# Carte_USB.net
KiCad netlist of a schematic drawn in EAGLE
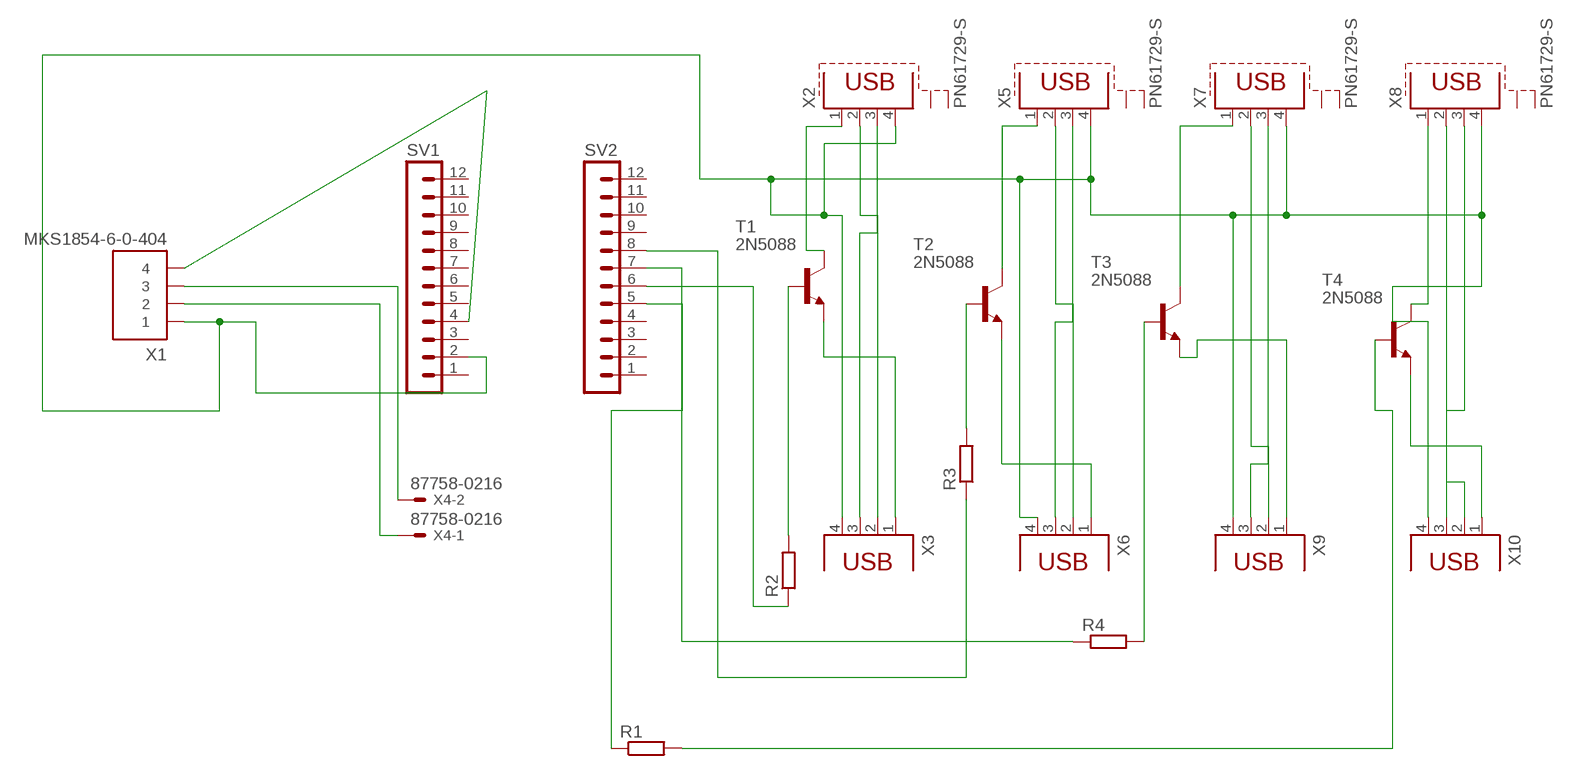
[diagram p0: schematic, sheet 1]

(export (version "E")
  (design (tool "Eeschema 10.0.6"))
  (components
    (comp (ref "R1")
      (value "R-EU_0207/10")
      (footprint "eagle-import:0207_10")
      (libsource (lib "eagle-import") (part "R-EU_0207/10"))
    )
    (comp (ref "R2")
      (value "R-EU_0207/10")
      (footprint "eagle-import:0207_10")
      (libsource (lib "eagle-import") (part "R-EU_0207/10"))
    )
    (comp (ref "R3")
      (value "R-EU_0207/10")
      (footprint "eagle-import:0207_10")
      (libsource (lib "eagle-import") (part "R-EU_0207/10"))
    )
    (comp (ref "R4")
      (value "R-EU_0207/10")
      (footprint "eagle-import:0207_10")
      (libsource (lib "eagle-import") (part "R-EU_0207/10"))
    )
    (comp (ref "SV1")
      (value "MA12-1")
      (footprint "eagle-import:MA12-1")
      (libsource (lib "eagle-import") (part "MA12-1"))
    )
    (comp (ref "SV2")
      (value "MA12-1")
      (footprint "eagle-import:MA12-1")
      (libsource (lib "eagle-import") (part "MA12-1"))
    )
    (comp (ref "T1")
      (value "2N5088")
      (footprint "eagle-import:TO92")
      (libsource (lib "eagle-import") (part "2N5088"))
    )
    (comp (ref "T2")
      (value "2N5088")
      (footprint "eagle-import:TO92")
      (libsource (lib "eagle-import") (part "2N5088"))
    )
    (comp (ref "T3")
      (value "2N5088")
      (footprint "eagle-import:TO92")
      (libsource (lib "eagle-import") (part "2N5088"))
    )
    (comp (ref "T4")
      (value "2N5088")
      (footprint "eagle-import:TO92")
      (libsource (lib "eagle-import") (part "2N5088"))
    )
    (comp (ref "X1")
      (value "MKS1854-6-0-404")
      (footprint "eagle-import:MKS1854-6-0-404")
      (libsource (lib "eagle-import") (part "MKS1854-6-0-404"))
    )
    (comp (ref "X2")
      (value "PN61729-S")
      (footprint "eagle-import:PN61729-S")
      (libsource (lib "eagle-import") (part "PN61729-S"))
    )
    (comp (ref "X3")
      (value "PN87520")
      (footprint "eagle-import:PN87520")
      (libsource (lib "eagle-import") (part "PN87520"))
    )
    (comp (ref "X4")
      (value "87758-0216")
      (footprint "eagle-import:87758-0216")
      (libsource (lib "eagle-import") (part "87758-0216"))
    )
    (comp (ref "X5")
      (value "PN61729-S")
      (footprint "eagle-import:PN61729-S")
      (libsource (lib "eagle-import") (part "PN61729-S"))
    )
    (comp (ref "X6")
      (value "PN87520")
      (footprint "eagle-import:PN87520")
      (libsource (lib "eagle-import") (part "PN87520"))
    )
    (comp (ref "X7")
      (value "PN61729-S")
      (footprint "eagle-import:PN61729-S")
      (libsource (lib "eagle-import") (part "PN61729-S"))
    )
    (comp (ref "X8")
      (value "PN61729-S")
      (footprint "eagle-import:PN61729-S")
      (libsource (lib "eagle-import") (part "PN61729-S"))
    )
    (comp (ref "X9")
      (value "PN87520")
      (footprint "eagle-import:PN87520")
      (libsource (lib "eagle-import") (part "PN87520"))
    )
    (comp (ref "X10")
      (value "PN87520")
      (footprint "eagle-import:PN87520")
      (libsource (lib "eagle-import") (part "PN87520"))
    )
  )
  (nets
    (net (code "1") (name "Net-(R1-Pad1)") (class "Default")
      (node (ref "R1") (pin "1") (pinfunction "1_1") (pintype "passive"))
      (node (ref "SV2") (pin "5") (pinfunction "5_5") (pintype "passive"))
    )
    (net (code "2") (name "Net-(R2-Pad1)") (class "Default")
      (node (ref "R2") (pin "1") (pinfunction "1_1") (pintype "passive"))
      (node (ref "SV2") (pin "6") (pinfunction "6_6") (pintype "passive"))
    )
    (net (code "3") (name "Net-(R3-Pad1)") (class "Default")
      (node (ref "R3") (pin "1") (pinfunction "1_1") (pintype "passive"))
      (node (ref "SV2") (pin "8") (pinfunction "8_8") (pintype "passive"))
    )
    (net (code "4") (name "Net-(R4-Pad1)") (class "Default")
      (node (ref "R4") (pin "1") (pinfunction "1_1") (pintype "passive"))
      (node (ref "SV2") (pin "7") (pinfunction "7_7") (pintype "passive"))
    )
    (net (code "5") (name "Net-(SV1-Pad2)") (class "Default")
      (node (ref "SV1") (pin "2") (pinfunction "2_2") (pintype "passive"))
      (node (ref "X1") (pin "1") (pinfunction "1_1") (pintype "input"))
      (node (ref "X10") (pin "4") (pinfunction "4_4") (pintype "passive"))
      (node (ref "X2") (pin "4") (pinfunction "4_4") (pintype "passive"))
      (node (ref "X3") (pin "4") (pinfunction "4_4") (pintype "passive"))
      (node (ref "X5") (pin "4") (pinfunction "4_4") (pintype "passive"))
      (node (ref "X6") (pin "4") (pinfunction "4_4") (pintype "passive"))
      (node (ref "X7") (pin "4") (pinfunction "4_4") (pintype "passive"))
      (node (ref "X8") (pin "4") (pinfunction "4_4") (pintype "passive"))
      (node (ref "X9") (pin "4") (pinfunction "4_4") (pintype "passive"))
    )
    (net (code "6") (name "Net-(SV1-Pad4)") (class "Default")
      (node (ref "SV1") (pin "4") (pinfunction "4_4") (pintype "passive"))
      (node (ref "X1") (pin "4") (pinfunction "4_4") (pintype "input"))
    )
    (net (code "7") (name "Net-(T1-B)") (class "Default")
      (node (ref "R2") (pin "2") (pinfunction "2_2") (pintype "passive"))
      (node (ref "T1") (pin "2") (pinfunction "B_2") (pintype "passive"))
    )
    (net (code "8") (name "Net-(T1-C)") (class "Default")
      (node (ref "T1") (pin "1") (pinfunction "C_1") (pintype "passive"))
      (node (ref "X2") (pin "1") (pinfunction "1_1") (pintype "passive"))
    )
    (net (code "9") (name "Net-(T1-E)") (class "Default")
      (node (ref "T1") (pin "3") (pinfunction "E_3") (pintype "passive"))
      (node (ref "X3") (pin "1") (pinfunction "1_1") (pintype "passive"))
    )
    (net (code "10") (name "Net-(T2-B)") (class "Default")
      (node (ref "R3") (pin "2") (pinfunction "2_2") (pintype "passive"))
      (node (ref "T2") (pin "2") (pinfunction "B_2") (pintype "passive"))
    )
    (net (code "11") (name "Net-(T2-C)") (class "Default")
      (node (ref "T2") (pin "1") (pinfunction "C_1") (pintype "passive"))
      (node (ref "X5") (pin "1") (pinfunction "1_1") (pintype "passive"))
    )
    (net (code "12") (name "Net-(T2-E)") (class "Default")
      (node (ref "T2") (pin "3") (pinfunction "E_3") (pintype "passive"))
      (node (ref "X6") (pin "1") (pinfunction "1_1") (pintype "passive"))
    )
    (net (code "13") (name "Net-(T3-B)") (class "Default")
      (node (ref "R4") (pin "2") (pinfunction "2_2") (pintype "passive"))
      (node (ref "T3") (pin "2") (pinfunction "B_2") (pintype "passive"))
    )
    (net (code "14") (name "Net-(T3-C)") (class "Default")
      (node (ref "T3") (pin "1") (pinfunction "C_1") (pintype "passive"))
      (node (ref "X7") (pin "1") (pinfunction "1_1") (pintype "passive"))
    )
    (net (code "15") (name "Net-(T3-E)") (class "Default")
      (node (ref "T3") (pin "3") (pinfunction "E_3") (pintype "passive"))
      (node (ref "X9") (pin "1") (pinfunction "1_1") (pintype "passive"))
    )
    (net (code "16") (name "Net-(T4-B)") (class "Default")
      (node (ref "R1") (pin "2") (pinfunction "2_2") (pintype "passive"))
      (node (ref "T4") (pin "2") (pinfunction "B_2") (pintype "passive"))
    )
    (net (code "17") (name "Net-(T4-C)") (class "Default")
      (node (ref "T4") (pin "1") (pinfunction "C_1") (pintype "passive"))
      (node (ref "X8") (pin "1") (pinfunction "1_1") (pintype "passive"))
    )
    (net (code "18") (name "Net-(T4-E)") (class "Default")
      (node (ref "T4") (pin "3") (pinfunction "E_3") (pintype "passive"))
      (node (ref "X10") (pin "1") (pinfunction "1_1") (pintype "passive"))
    )
    (net (code "19") (name "Net-(X2-Pad2)") (class "Default")
      (node (ref "X2") (pin "2") (pinfunction "2_2") (pintype "passive"))
      (node (ref "X3") (pin "2") (pinfunction "2_2") (pintype "passive"))
    )
    (net (code "20") (name "Net-(X2-Pad3)") (class "Default")
      (node (ref "X2") (pin "3") (pinfunction "3_3") (pintype "passive"))
      (node (ref "X3") (pin "3") (pinfunction "3_3") (pintype "passive"))
    )
    (net (code "21") (name "Net-(X4A-S)") (class "Default")
      (node (ref "X1") (pin "2") (pinfunction "2_2") (pintype "input"))
      (node (ref "X4") (pin "1") (pinfunction "S_1") (pintype "passive"))
    )
    (net (code "22") (name "Net-(X4B-S)") (class "Default")
      (node (ref "X1") (pin "3") (pinfunction "3_3") (pintype "input"))
      (node (ref "X4") (pin "2") (pinfunction "S_2") (pintype "passive"))
    )
    (net (code "23") (name "Net-(X5-Pad2)") (class "Default")
      (node (ref "X5") (pin "2") (pinfunction "2_2") (pintype "passive"))
      (node (ref "X6") (pin "2") (pinfunction "2_2") (pintype "passive"))
    )
    (net (code "24") (name "Net-(X5-Pad3)") (class "Default")
      (node (ref "X5") (pin "3") (pinfunction "3_3") (pintype "passive"))
      (node (ref "X6") (pin "3") (pinfunction "3_3") (pintype "passive"))
    )
    (net (code "25") (name "Net-(X7-Pad2)") (class "Default")
      (node (ref "X7") (pin "2") (pinfunction "2_2") (pintype "passive"))
      (node (ref "X9") (pin "2") (pinfunction "2_2") (pintype "passive"))
    )
    (net (code "26") (name "Net-(X7-Pad3)") (class "Default")
      (node (ref "X7") (pin "3") (pinfunction "3_3") (pintype "passive"))
      (node (ref "X9") (pin "3") (pinfunction "3_3") (pintype "passive"))
    )
    (net (code "27") (name "Net-(X10-Pad2)") (class "Default")
      (node (ref "X10") (pin "2") (pinfunction "2_2") (pintype "passive"))
      (node (ref "X8") (pin "2") (pinfunction "2_2") (pintype "passive"))
    )
    (net (code "28") (name "Net-(X10-Pad3)") (class "Default")
      (node (ref "X10") (pin "3") (pinfunction "3_3") (pintype "passive"))
      (node (ref "X8") (pin "3") (pinfunction "3_3") (pintype "passive"))
    )
    (net (code "29") (name "unconnected-(SV1-Pad1)") (class "Default")
      (node (ref "SV1") (pin "1") (pinfunction "1_1") (pintype "passive"))
    )
    (net (code "30") (name "unconnected-(SV1-Pad3)") (class "Default")
      (node (ref "SV1") (pin "3") (pinfunction "3_3") (pintype "passive"))
    )
    (net (code "31") (name "unconnected-(SV1-Pad5)") (class "Default")
      (node (ref "SV1") (pin "5") (pinfunction "5_5") (pintype "passive"))
    )
    (net (code "32") (name "unconnected-(SV1-Pad6)") (class "Default")
      (node (ref "SV1") (pin "6") (pinfunction "6_6") (pintype "passive"))
    )
    (net (code "33") (name "unconnected-(SV1-Pad7)") (class "Default")
      (node (ref "SV1") (pin "7") (pinfunction "7_7") (pintype "passive"))
    )
    (net (code "34") (name "unconnected-(SV1-Pad8)") (class "Default")
      (node (ref "SV1") (pin "8") (pinfunction "8_8") (pintype "passive"))
    )
    (net (code "35") (name "unconnected-(SV1-Pad9)") (class "Default")
      (node (ref "SV1") (pin "9") (pinfunction "9_9") (pintype "passive"))
    )
    (net (code "36") (name "unconnected-(SV1-Pad10)") (class "Default")
      (node (ref "SV1") (pin "10") (pinfunction "10_10") (pintype "passive"))
    )
    (net (code "37") (name "unconnected-(SV1-Pad11)") (class "Default")
      (node (ref "SV1") (pin "11") (pinfunction "11_11") (pintype "passive"))
    )
    (net (code "38") (name "unconnected-(SV1-Pad12)") (class "Default")
      (node (ref "SV1") (pin "12") (pinfunction "12_12") (pintype "passive"))
    )
    (net (code "39") (name "unconnected-(SV2-Pad1)") (class "Default")
      (node (ref "SV2") (pin "1") (pinfunction "1_1") (pintype "passive"))
    )
    (net (code "40") (name "unconnected-(SV2-Pad2)") (class "Default")
      (node (ref "SV2") (pin "2") (pinfunction "2_2") (pintype "passive"))
    )
    (net (code "41") (name "unconnected-(SV2-Pad3)") (class "Default")
      (node (ref "SV2") (pin "3") (pinfunction "3_3") (pintype "passive"))
    )
    (net (code "42") (name "unconnected-(SV2-Pad4)") (class "Default")
      (node (ref "SV2") (pin "4") (pinfunction "4_4") (pintype "passive"))
    )
    (net (code "43") (name "unconnected-(SV2-Pad9)") (class "Default")
      (node (ref "SV2") (pin "9") (pinfunction "9_9") (pintype "passive"))
    )
    (net (code "44") (name "unconnected-(SV2-Pad10)") (class "Default")
      (node (ref "SV2") (pin "10") (pinfunction "10_10") (pintype "passive"))
    )
    (net (code "45") (name "unconnected-(SV2-Pad11)") (class "Default")
      (node (ref "SV2") (pin "11") (pinfunction "11_11") (pintype "passive"))
    )
    (net (code "46") (name "unconnected-(SV2-Pad12)") (class "Default")
      (node (ref "SV2") (pin "12") (pinfunction "12_12") (pintype "passive"))
    )
    (net (code "47") (name "unconnected-(X2-PadS1)") (class "Default")
      (node (ref "X2") (pin "S1") (pinfunction "S1_S1") (pintype "passive"))
    )
    (net (code "48") (name "unconnected-(X2-PadS2)") (class "Default")
      (node (ref "X2") (pin "S2") (pinfunction "S2_S2") (pintype "passive"))
    )
    (net (code "49") (name "unconnected-(X5-PadS1)") (class "Default")
      (node (ref "X5") (pin "S1") (pinfunction "S1_S1") (pintype "passive"))
    )
    (net (code "50") (name "unconnected-(X5-PadS2)") (class "Default")
      (node (ref "X5") (pin "S2") (pinfunction "S2_S2") (pintype "passive"))
    )
    (net (code "51") (name "unconnected-(X7-PadS1)") (class "Default")
      (node (ref "X7") (pin "S1") (pinfunction "S1_S1") (pintype "passive"))
    )
    (net (code "52") (name "unconnected-(X7-PadS2)") (class "Default")
      (node (ref "X7") (pin "S2") (pinfunction "S2_S2") (pintype "passive"))
    )
    (net (code "53") (name "unconnected-(X8-PadS1)") (class "Default")
      (node (ref "X8") (pin "S1") (pinfunction "S1_S1") (pintype "passive"))
    )
    (net (code "54") (name "unconnected-(X8-PadS2)") (class "Default")
      (node (ref "X8") (pin "S2") (pinfunction "S2_S2") (pintype "passive"))
    )
  )
)
